# 01_LSH-120.net
KiCad netlist of a schematic drawn in Altium Designer
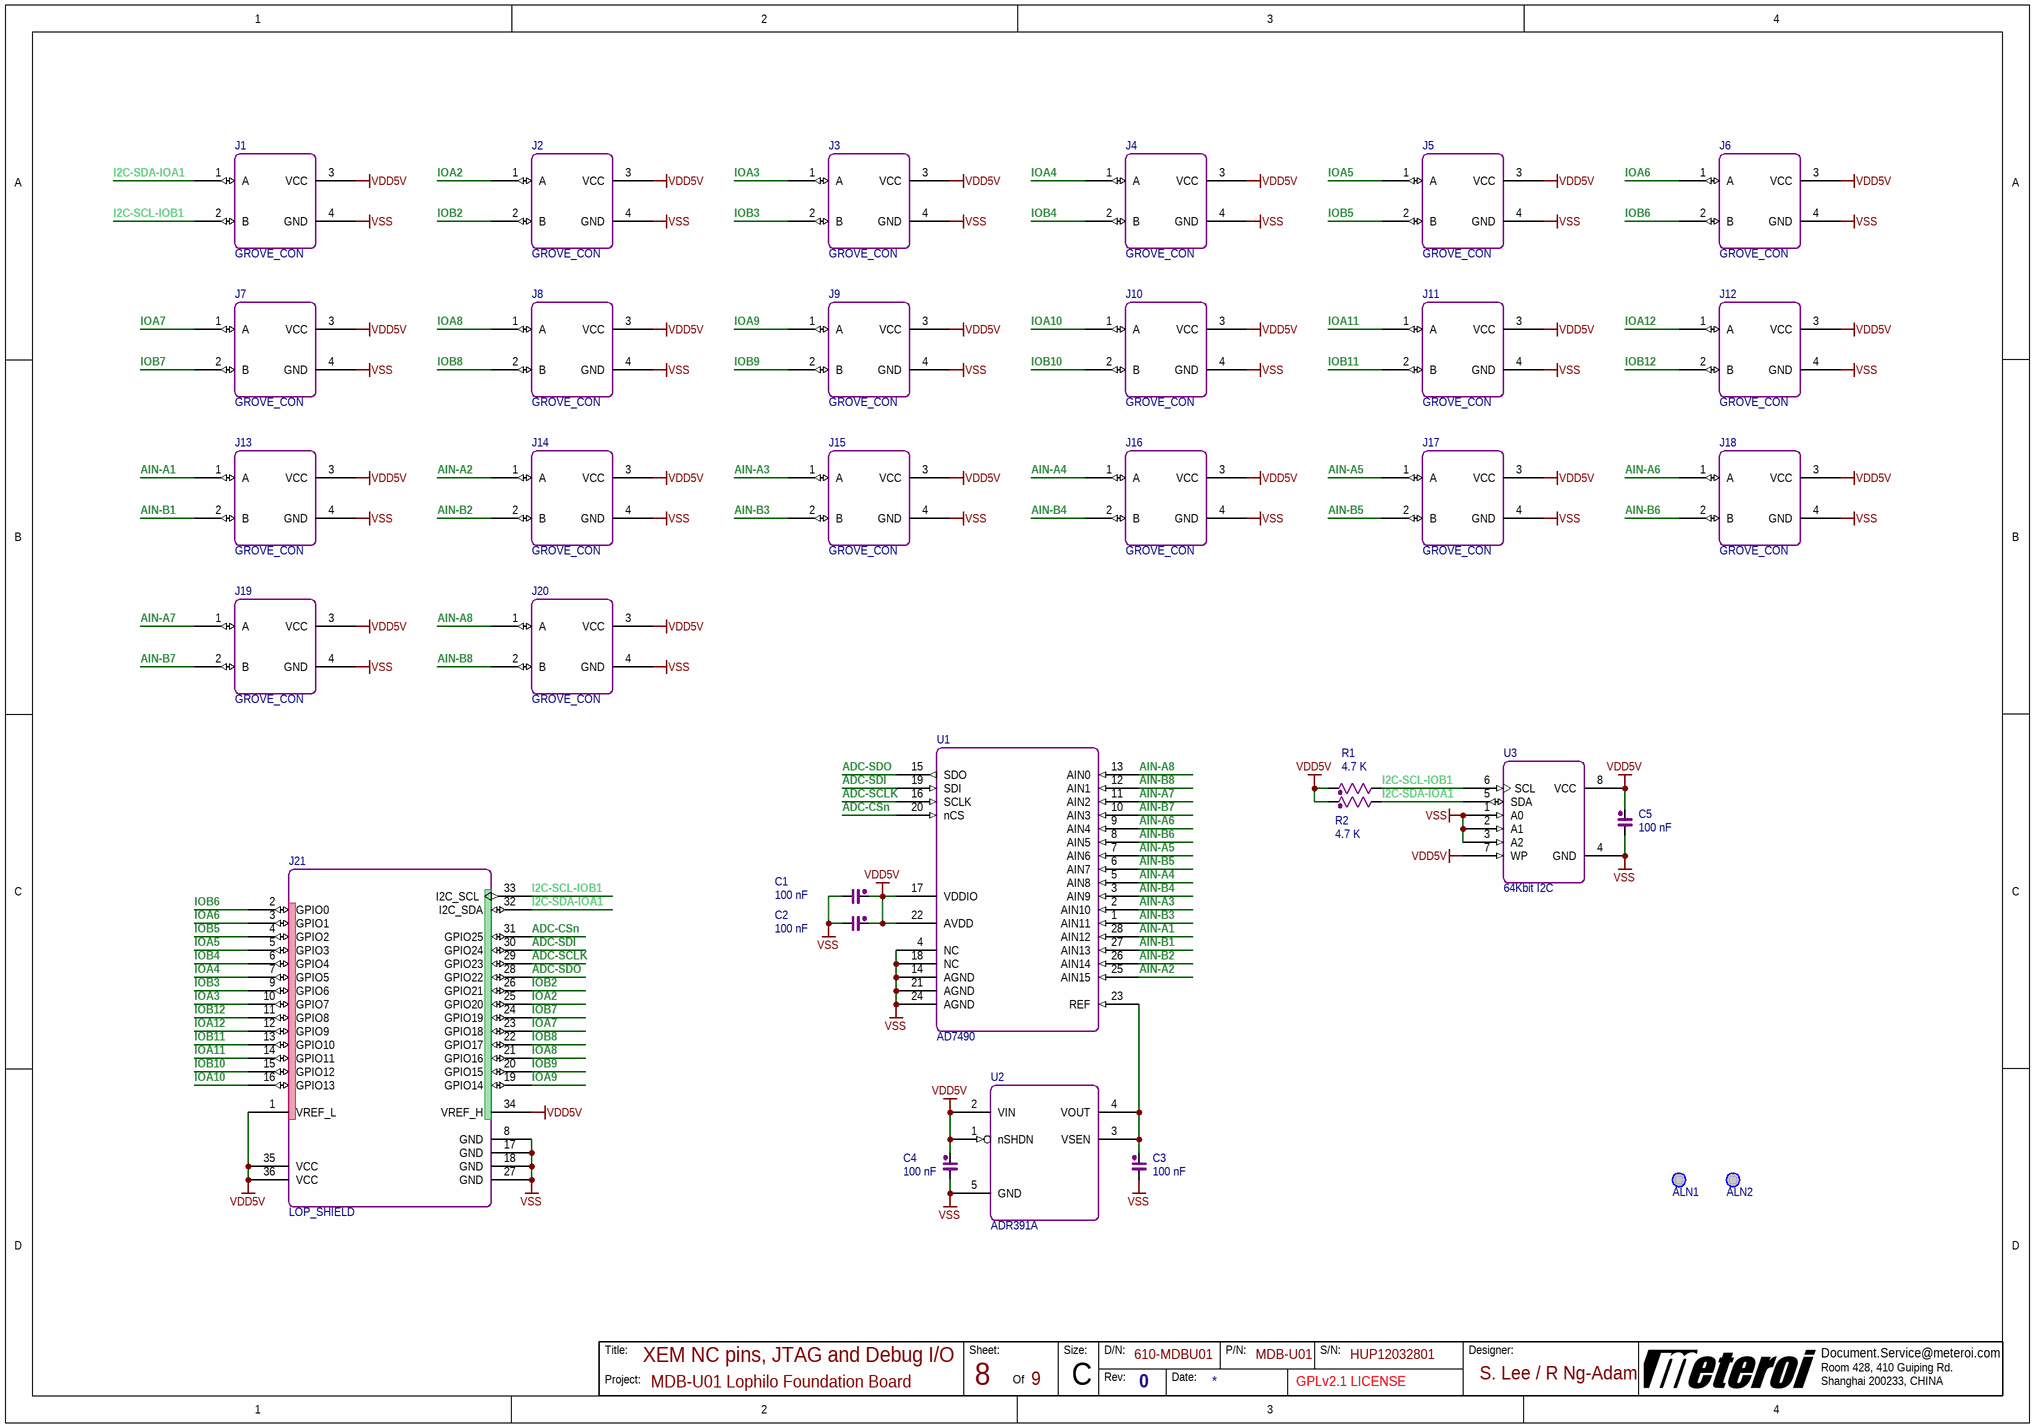
[diagram p0: 01_LSH-120.SchDoc]

(export (version "E")
  (design (tool "Eeschema 10.0.6"))
  (components
    (comp (ref "ALN1")
      (value "Assembly Optical Align")
      (footprint "ALIGN_1")
      (fields
        (field (name "PARTNUMBER") "0")
        (field (name "PUBLISHER") "Cowin")
        (field (name "DESIGNER") "shyul")
      )
      (libsource (lib "PCBElement_Manufacture") (part "ALIGN"))
    )
    (comp (ref "ALN2")
      (value "Assembly Optical Align")
      (footprint "ALIGN_1")
      (fields
        (field (name "PARTNUMBER") "0")
        (field (name "PUBLISHER") "Cowin")
        (field (name "DESIGNER") "shyul")
      )
      (libsource (lib "PCBElement_Manufacture") (part "ALIGN"))
    )
    (comp (ref "C1")
      (value "100 nF")
      (footprint "0603A1")
      (description "Normal Capacitor")
      (fields
        (field (name "PARTNUMBER") "0")
        (field (name "PUBLISHER") "Cowin")
        (field (name "DESIGNER") "shyul")
      )
      (libsource (lib "") (part "CAP_1"))
    )
    (comp (ref "C2")
      (value "100 nF")
      (footprint "0603A1")
      (description "Normal Capacitor")
      (fields
        (field (name "PARTNUMBER") "0")
        (field (name "PUBLISHER") "Cowin")
        (field (name "DESIGNER") "shyul")
      )
      (libsource (lib "") (part "CAP_1"))
    )
    (comp (ref "C3")
      (value "100 nF")
      (footprint "0603A1")
      (description "Normal Capacitor")
      (fields
        (field (name "PARTNUMBER") "0")
        (field (name "PUBLISHER") "Cowin")
        (field (name "DESIGNER") "shyul")
      )
      (libsource (lib "Basc_1_Passive") (part "CAP"))
    )
    (comp (ref "C4")
      (value "100 nF")
      (footprint "0603A1")
      (description "Normal Capacitor")
      (fields
        (field (name "PARTNUMBER") "0")
        (field (name "PUBLISHER") "Cowin")
        (field (name "DESIGNER") "shyul")
      )
      (libsource (lib "Basc_1_Passive") (part "CAP"))
    )
    (comp (ref "C5")
      (value "100 nF")
      (footprint "0603A1")
      (description "Normal Capacitor")
      (fields
        (field (name "PARTNUMBER") "0")
        (field (name "PUBLISHER") "Cowin")
        (field (name "DESIGNER") "shyul")
      )
      (libsource (lib "Basc_1_Passive") (part "CAP"))
    )
    (comp (ref "J1")
      (value "GROVE_CON")
      (footprint "PHB-4A")
      (description "Grove Connector")
      (fields (field (name "PUBLISHER") "Cowin") (field (name "DESIGNER") "shyul"))
      (libsource (lib "PCB_LSH-120") (part "GROVE_CON"))
    )
    (comp (ref "J2")
      (value "GROVE_CON")
      (footprint "PHB-4A")
      (description "Grove Connector")
      (fields (field (name "PUBLISHER") "Cowin") (field (name "DESIGNER") "shyul"))
      (libsource (lib "PCB_LSH-120") (part "GROVE_CON"))
    )
    (comp (ref "J3")
      (value "GROVE_CON")
      (footprint "PHB-4A")
      (description "Grove Connector")
      (fields (field (name "PUBLISHER") "Cowin") (field (name "DESIGNER") "shyul"))
      (libsource (lib "PCB_LSH-120") (part "GROVE_CON"))
    )
    (comp (ref "J4")
      (value "GROVE_CON")
      (footprint "PHB-4A")
      (description "Grove Connector")
      (fields (field (name "PUBLISHER") "Cowin") (field (name "DESIGNER") "shyul"))
      (libsource (lib "PCB_LSH-120") (part "GROVE_CON"))
    )
    (comp (ref "J5")
      (value "GROVE_CON")
      (footprint "PHB-4A")
      (description "Grove Connector")
      (fields (field (name "PUBLISHER") "Cowin") (field (name "DESIGNER") "shyul"))
      (libsource (lib "PCB_LSH-120") (part "GROVE_CON"))
    )
    (comp (ref "J6")
      (value "GROVE_CON")
      (footprint "PHB-4A")
      (description "Grove Connector")
      (fields (field (name "PUBLISHER") "Cowin") (field (name "DESIGNER") "shyul"))
      (libsource (lib "PCB_LSH-120") (part "GROVE_CON"))
    )
    (comp (ref "J7")
      (value "GROVE_CON")
      (footprint "PHB-4A")
      (description "Grove Connector")
      (fields (field (name "PUBLISHER") "Cowin") (field (name "DESIGNER") "shyul"))
      (libsource (lib "PCB_LSH-120") (part "GROVE_CON"))
    )
    (comp (ref "J8")
      (value "GROVE_CON")
      (footprint "PHB-4A")
      (description "Grove Connector")
      (fields (field (name "PUBLISHER") "Cowin") (field (name "DESIGNER") "shyul"))
      (libsource (lib "PCB_LSH-120") (part "GROVE_CON"))
    )
    (comp (ref "J9")
      (value "GROVE_CON")
      (footprint "PHB-4A")
      (description "Grove Connector")
      (fields (field (name "PUBLISHER") "Cowin") (field (name "DESIGNER") "shyul"))
      (libsource (lib "PCB_LSH-120") (part "GROVE_CON"))
    )
    (comp (ref "J10")
      (value "GROVE_CON")
      (footprint "PHB-4A")
      (description "Grove Connector")
      (fields (field (name "PUBLISHER") "Cowin") (field (name "DESIGNER") "shyul"))
      (libsource (lib "PCB_LSH-120") (part "GROVE_CON"))
    )
    (comp (ref "J11")
      (value "GROVE_CON")
      (footprint "PHB-4A")
      (description "Grove Connector")
      (fields (field (name "PUBLISHER") "Cowin") (field (name "DESIGNER") "shyul"))
      (libsource (lib "PCB_LSH-120") (part "GROVE_CON"))
    )
    (comp (ref "J12")
      (value "GROVE_CON")
      (footprint "PHB-4A")
      (description "Grove Connector")
      (fields (field (name "PUBLISHER") "Cowin") (field (name "DESIGNER") "shyul"))
      (libsource (lib "PCB_LSH-120") (part "GROVE_CON"))
    )
    (comp (ref "J13")
      (value "GROVE_CON")
      (footprint "PHB-4A")
      (description "Grove Connector")
      (fields (field (name "PUBLISHER") "Cowin") (field (name "DESIGNER") "shyul"))
      (libsource (lib "PCB_LSH-120") (part "GROVE_CON"))
    )
    (comp (ref "J14")
      (value "GROVE_CON")
      (footprint "PHB-4A")
      (description "Grove Connector")
      (fields (field (name "PUBLISHER") "Cowin") (field (name "DESIGNER") "shyul"))
      (libsource (lib "PCB_LSH-120") (part "GROVE_CON"))
    )
    (comp (ref "J15")
      (value "GROVE_CON")
      (footprint "PHB-4A")
      (description "Grove Connector")
      (fields (field (name "PUBLISHER") "Cowin") (field (name "DESIGNER") "shyul"))
      (libsource (lib "PCB_LSH-120") (part "GROVE_CON"))
    )
    (comp (ref "J16")
      (value "GROVE_CON")
      (footprint "PHB-4A")
      (description "Grove Connector")
      (fields (field (name "PUBLISHER") "Cowin") (field (name "DESIGNER") "shyul"))
      (libsource (lib "PCB_LSH-120") (part "GROVE_CON"))
    )
    (comp (ref "J17")
      (value "GROVE_CON")
      (footprint "PHB-4A")
      (description "Grove Connector")
      (fields (field (name "PUBLISHER") "Cowin") (field (name "DESIGNER") "shyul"))
      (libsource (lib "PCB_LSH-120") (part "GROVE_CON"))
    )
    (comp (ref "J18")
      (value "GROVE_CON")
      (footprint "PHB-4A")
      (description "Grove Connector")
      (fields (field (name "PUBLISHER") "Cowin") (field (name "DESIGNER") "shyul"))
      (libsource (lib "PCB_LSH-120") (part "GROVE_CON"))
    )
    (comp (ref "J19")
      (value "GROVE_CON")
      (footprint "PHB-4A")
      (description "Grove Connector")
      (fields (field (name "PUBLISHER") "Cowin") (field (name "DESIGNER") "shyul"))
      (libsource (lib "PCB_LSH-120") (part "GROVE_CON"))
    )
    (comp (ref "J20")
      (value "GROVE_CON")
      (footprint "PHB-4A")
      (description "Grove Connector")
      (fields (field (name "PUBLISHER") "Cowin") (field (name "DESIGNER") "shyul"))
      (libsource (lib "PCB_LSH-120") (part "GROVE_CON"))
    )
    (comp (ref "J21")
      (value "LOP_SHIELD")
      (footprint "LOP_SHIELD_MOD")
      (description "Lophilo Shield Module Slot")
      (fields (field (name "PUBLISHER") "Cowin") (field (name "DESIGNER") "shyul"))
      (libsource (lib "PCB_LSH-100") (part "LOP_SHIELD_MOD"))
    )
    (comp (ref "R1")
      (value "4.7 K")
      (footprint "0603A2")
      (description "Normal Resistor")
      (fields
        (field (name "PARTNUMBER") "0")
        (field (name "DESIGNER") "shyul")
        (field (name "PUBLISHER") "Cowin")
      )
      (libsource (lib "Basc_1_Passive") (part "RES"))
    )
    (comp (ref "R2")
      (value "4.7 K")
      (footprint "0603A2")
      (description "Normal Resistor")
      (fields
        (field (name "PARTNUMBER") "0")
        (field (name "DESIGNER") "shyul")
        (field (name "PUBLISHER") "Cowin")
      )
      (libsource (lib "Basc_1_Passive") (part "RES"))
    )
    (comp (ref "U1")
      (value "AD7490")
      (footprint "TSSOP-28")
      (description "16 Inputs MUX ADC / 12-Bit 1Msps")
      (fields (field (name "PUBLISHER") "Cowin") (field (name "DESIGNER") "shyul"))
      (libsource (lib "PCB_LSH-120") (part "AD7490"))
    )
    (comp (ref "U2")
      (value "ADR391A")
      (footprint "SOT-23-5")
      (description "16 Inputs MUX ADC / 12-Bit 1Msps")
      (fields
        (field (name "PARTNUMBER") "ADR391AUJZ")
        (field (name "PUBLISHER") "Cowin")
        (field (name "DESIGNER") "shyul")
      )
      (libsource (lib "PCB_LSH-120") (part "ADR391"))
    )
    (comp (ref "U3")
      (value "64Kbit I2C")
      (footprint "SOIC-8S")
      (description "Generic 24 Series I2C ROM")
      (fields
        (field (name "PARTNUMBER") "24C08")
        (field (name "PUBLISHER") "Cowin")
        (field (name "DESIGNER") "shyul")
      )
      (libsource (lib "IC_03_MCU") (part "ROM_I2C_A"))
    )
  )
  (nets
    (net (code "1") (name "/ADC-CSn") (class "Default")
      (node (ref "J21") (pin "31") (pinfunction "GPIO25_31") (pintype "bidirectional"))
      (node (ref "U1") (pin "20") (pinfunction "nCS_20") (pintype "input"))
    )
    (net (code "2") (name "/ADC-SCLK") (class "Default")
      (node (ref "J21") (pin "29") (pinfunction "GPIO23_29") (pintype "bidirectional"))
      (node (ref "U1") (pin "16") (pinfunction "SCLK_16") (pintype "input"))
    )
    (net (code "3") (name "/ADC-SDI") (class "Default")
      (node (ref "J21") (pin "30") (pinfunction "GPIO24_30") (pintype "bidirectional"))
      (node (ref "U1") (pin "19") (pinfunction "SDI_19") (pintype "input"))
    )
    (net (code "4") (name "/ADC-SDO") (class "Default")
      (node (ref "J21") (pin "28") (pinfunction "GPIO22_28") (pintype "bidirectional"))
      (node (ref "U1") (pin "15") (pinfunction "SDO_15") (pintype "output"))
    )
    (net (code "5") (name "/AIN-A1") (class "Default")
      (node (ref "J13") (pin "1") (pinfunction "A_1") (pintype "bidirectional"))
      (node (ref "U1") (pin "28") (pinfunction "AIN12_28") (pintype "input"))
    )
    (net (code "6") (name "/AIN-A2") (class "Default")
      (node (ref "J14") (pin "1") (pinfunction "A_1") (pintype "bidirectional"))
      (node (ref "U1") (pin "25") (pinfunction "AIN15_25") (pintype "input"))
    )
    (net (code "7") (name "/AIN-A3") (class "Default")
      (node (ref "J15") (pin "1") (pinfunction "A_1") (pintype "bidirectional"))
      (node (ref "U1") (pin "2") (pinfunction "AIN10_2") (pintype "input"))
    )
    (net (code "8") (name "/AIN-A4") (class "Default")
      (node (ref "J16") (pin "1") (pinfunction "A_1") (pintype "bidirectional"))
      (node (ref "U1") (pin "5") (pinfunction "AIN8_5") (pintype "input"))
    )
    (net (code "9") (name "/AIN-A5") (class "Default")
      (node (ref "J17") (pin "1") (pinfunction "A_1") (pintype "bidirectional"))
      (node (ref "U1") (pin "7") (pinfunction "AIN6_7") (pintype "input"))
    )
    (net (code "10") (name "/AIN-A6") (class "Default")
      (node (ref "J18") (pin "1") (pinfunction "A_1") (pintype "bidirectional"))
      (node (ref "U1") (pin "9") (pinfunction "AIN4_9") (pintype "input"))
    )
    (net (code "11") (name "/AIN-A7") (class "Default")
      (node (ref "J19") (pin "1") (pinfunction "A_1") (pintype "bidirectional"))
      (node (ref "U1") (pin "11") (pinfunction "AIN2_11") (pintype "input"))
    )
    (net (code "12") (name "/AIN-A8") (class "Default")
      (node (ref "J20") (pin "1") (pinfunction "A_1") (pintype "bidirectional"))
      (node (ref "U1") (pin "13") (pinfunction "AIN0_13") (pintype "input"))
    )
    (net (code "13") (name "/AIN-B1") (class "Default")
      (node (ref "J13") (pin "2") (pinfunction "B_2") (pintype "bidirectional"))
      (node (ref "U1") (pin "27") (pinfunction "AIN13_27") (pintype "input"))
    )
    (net (code "14") (name "/AIN-B2") (class "Default")
      (node (ref "J14") (pin "2") (pinfunction "B_2") (pintype "bidirectional"))
      (node (ref "U1") (pin "26") (pinfunction "AIN14_26") (pintype "input"))
    )
    (net (code "15") (name "/AIN-B3") (class "Default")
      (node (ref "J15") (pin "2") (pinfunction "B_2") (pintype "bidirectional"))
      (node (ref "U1") (pin "1") (pinfunction "AIN11_1") (pintype "input"))
    )
    (net (code "16") (name "/AIN-B4") (class "Default")
      (node (ref "J16") (pin "2") (pinfunction "B_2") (pintype "bidirectional"))
      (node (ref "U1") (pin "3") (pinfunction "AIN9_3") (pintype "input"))
    )
    (net (code "17") (name "/AIN-B5") (class "Default")
      (node (ref "J17") (pin "2") (pinfunction "B_2") (pintype "bidirectional"))
      (node (ref "U1") (pin "6") (pinfunction "AIN7_6") (pintype "input"))
    )
    (net (code "18") (name "/AIN-B6") (class "Default")
      (node (ref "J18") (pin "2") (pinfunction "B_2") (pintype "bidirectional"))
      (node (ref "U1") (pin "8") (pinfunction "AIN5_8") (pintype "input"))
    )
    (net (code "19") (name "/AIN-B7") (class "Default")
      (node (ref "J19") (pin "2") (pinfunction "B_2") (pintype "bidirectional"))
      (node (ref "U1") (pin "10") (pinfunction "AIN3_10") (pintype "input"))
    )
    (net (code "20") (name "/AIN-B8") (class "Default")
      (node (ref "J20") (pin "2") (pinfunction "B_2") (pintype "bidirectional"))
      (node (ref "U1") (pin "12") (pinfunction "AIN1_12") (pintype "input"))
    )
    (net (code "21") (name "/I2C-SCL-IOB1") (class "Default")
      (node (ref "J1") (pin "2") (pinfunction "B_2") (pintype "bidirectional"))
      (node (ref "J21") (pin "33") (pinfunction "I2C_SCL_33") (pintype "output"))
      (node (ref "R1") (pin "1") (pinfunction "1_1") (pintype "passive"))
      (node (ref "U3") (pin "6") (pinfunction "SCL_6") (pintype "input"))
    )
    (net (code "22") (name "/I2C-SDA-IOA1") (class "Default")
      (node (ref "J1") (pin "1") (pinfunction "A_1") (pintype "bidirectional"))
      (node (ref "J21") (pin "32") (pinfunction "I2C_SDA_32") (pintype "bidirectional"))
      (node (ref "R2") (pin "1") (pinfunction "1_1") (pintype "passive"))
      (node (ref "U3") (pin "5") (pinfunction "SDA_5") (pintype "bidirectional"))
    )
    (net (code "23") (name "/IOA2") (class "Default")
      (node (ref "J2") (pin "1") (pinfunction "A_1") (pintype "bidirectional"))
      (node (ref "J21") (pin "25") (pinfunction "GPIO20_25") (pintype "bidirectional"))
    )
    (net (code "24") (name "/IOA3") (class "Default")
      (node (ref "J21") (pin "10") (pinfunction "GPIO7_10") (pintype "bidirectional"))
      (node (ref "J3") (pin "1") (pinfunction "A_1") (pintype "bidirectional"))
    )
    (net (code "25") (name "/IOA4") (class "Default")
      (node (ref "J21") (pin "7") (pinfunction "GPIO5_7") (pintype "bidirectional"))
      (node (ref "J4") (pin "1") (pinfunction "A_1") (pintype "bidirectional"))
    )
    (net (code "26") (name "/IOA5") (class "Default")
      (node (ref "J21") (pin "5") (pinfunction "GPIO3_5") (pintype "bidirectional"))
      (node (ref "J5") (pin "1") (pinfunction "A_1") (pintype "bidirectional"))
    )
    (net (code "27") (name "/IOA6") (class "Default")
      (node (ref "J21") (pin "3") (pinfunction "GPIO1_3") (pintype "bidirectional"))
      (node (ref "J6") (pin "1") (pinfunction "A_1") (pintype "bidirectional"))
    )
    (net (code "28") (name "/IOA7") (class "Default")
      (node (ref "J21") (pin "23") (pinfunction "GPIO18_23") (pintype "bidirectional"))
      (node (ref "J7") (pin "1") (pinfunction "A_1") (pintype "bidirectional"))
    )
    (net (code "29") (name "/IOA8") (class "Default")
      (node (ref "J21") (pin "21") (pinfunction "GPIO16_21") (pintype "bidirectional"))
      (node (ref "J8") (pin "1") (pinfunction "A_1") (pintype "bidirectional"))
    )
    (net (code "30") (name "/IOA9") (class "Default")
      (node (ref "J21") (pin "19") (pinfunction "GPIO14_19") (pintype "bidirectional"))
      (node (ref "J9") (pin "1") (pinfunction "A_1") (pintype "bidirectional"))
    )
    (net (code "31") (name "/IOA10") (class "Default")
      (node (ref "J10") (pin "1") (pinfunction "A_1") (pintype "bidirectional"))
      (node (ref "J21") (pin "16") (pinfunction "GPIO13_16") (pintype "bidirectional"))
    )
    (net (code "32") (name "/IOA11") (class "Default")
      (node (ref "J11") (pin "1") (pinfunction "A_1") (pintype "bidirectional"))
      (node (ref "J21") (pin "14") (pinfunction "GPIO11_14") (pintype "bidirectional"))
    )
    (net (code "33") (name "/IOA12") (class "Default")
      (node (ref "J12") (pin "1") (pinfunction "A_1") (pintype "bidirectional"))
      (node (ref "J21") (pin "12") (pinfunction "GPIO9_12") (pintype "bidirectional"))
    )
    (net (code "34") (name "/IOB2") (class "Default")
      (node (ref "J2") (pin "2") (pinfunction "B_2") (pintype "bidirectional"))
      (node (ref "J21") (pin "26") (pinfunction "GPIO21_26") (pintype "bidirectional"))
    )
    (net (code "35") (name "/IOB3") (class "Default")
      (node (ref "J21") (pin "9") (pinfunction "GPIO6_9") (pintype "bidirectional"))
      (node (ref "J3") (pin "2") (pinfunction "B_2") (pintype "bidirectional"))
    )
    (net (code "36") (name "/IOB4") (class "Default")
      (node (ref "J21") (pin "6") (pinfunction "GPIO4_6") (pintype "bidirectional"))
      (node (ref "J4") (pin "2") (pinfunction "B_2") (pintype "bidirectional"))
    )
    (net (code "37") (name "/IOB5") (class "Default")
      (node (ref "J21") (pin "4") (pinfunction "GPIO2_4") (pintype "bidirectional"))
      (node (ref "J5") (pin "2") (pinfunction "B_2") (pintype "bidirectional"))
    )
    (net (code "38") (name "/IOB6") (class "Default")
      (node (ref "J21") (pin "2") (pinfunction "GPIO0_2") (pintype "bidirectional"))
      (node (ref "J6") (pin "2") (pinfunction "B_2") (pintype "bidirectional"))
    )
    (net (code "39") (name "/IOB7") (class "Default")
      (node (ref "J21") (pin "24") (pinfunction "GPIO19_24") (pintype "bidirectional"))
      (node (ref "J7") (pin "2") (pinfunction "B_2") (pintype "bidirectional"))
    )
    (net (code "40") (name "/IOB8") (class "Default")
      (node (ref "J21") (pin "22") (pinfunction "GPIO17_22") (pintype "bidirectional"))
      (node (ref "J8") (pin "2") (pinfunction "B_2") (pintype "bidirectional"))
    )
    (net (code "41") (name "/IOB9") (class "Default")
      (node (ref "J21") (pin "20") (pinfunction "GPIO15_20") (pintype "bidirectional"))
      (node (ref "J9") (pin "2") (pinfunction "B_2") (pintype "bidirectional"))
    )
    (net (code "42") (name "/IOB10") (class "Default")
      (node (ref "J10") (pin "2") (pinfunction "B_2") (pintype "bidirectional"))
      (node (ref "J21") (pin "15") (pinfunction "GPIO12_15") (pintype "bidirectional"))
    )
    (net (code "43") (name "/IOB11") (class "Default")
      (node (ref "J11") (pin "2") (pinfunction "B_2") (pintype "bidirectional"))
      (node (ref "J21") (pin "13") (pinfunction "GPIO10_13") (pintype "bidirectional"))
    )
    (net (code "44") (name "/IOB12") (class "Default")
      (node (ref "J12") (pin "2") (pinfunction "B_2") (pintype "bidirectional"))
      (node (ref "J21") (pin "11") (pinfunction "GPIO8_11") (pintype "bidirectional"))
    )
    (net (code "45") (name "Net-(U1-REF)") (class "Default")
      (node (ref "C3") (pin "2") (pinfunction "2_2") (pintype "passive"))
      (node (ref "U1") (pin "23") (pinfunction "REF_23") (pintype "input"))
      (node (ref "U2") (pin "3") (pinfunction "VSEN_3") (pintype "passive"))
      (node (ref "U2") (pin "4") (pinfunction "VOUT_4") (pintype "passive"))
    )
    (net (code "46") (name "VDD5V") (class "Default")
      (node (ref "C1") (pin "2") (pinfunction "2_2") (pintype "passive"))
      (node (ref "C2") (pin "2") (pinfunction "2_2") (pintype "passive"))
      (node (ref "C4") (pin "2") (pinfunction "2_2") (pintype "passive"))
      (node (ref "C5") (pin "2") (pinfunction "2_2") (pintype "passive"))
      (node (ref "J1") (pin "3") (pinfunction "VCC_3") (pintype "passive"))
      (node (ref "J10") (pin "3") (pinfunction "VCC_3") (pintype "passive"))
      (node (ref "J11") (pin "3") (pinfunction "VCC_3") (pintype "passive"))
      (node (ref "J12") (pin "3") (pinfunction "VCC_3") (pintype "passive"))
      (node (ref "J13") (pin "3") (pinfunction "VCC_3") (pintype "passive"))
      (node (ref "J14") (pin "3") (pinfunction "VCC_3") (pintype "passive"))
      (node (ref "J15") (pin "3") (pinfunction "VCC_3") (pintype "passive"))
      (node (ref "J16") (pin "3") (pinfunction "VCC_3") (pintype "passive"))
      (node (ref "J17") (pin "3") (pinfunction "VCC_3") (pintype "passive"))
      (node (ref "J18") (pin "3") (pinfunction "VCC_3") (pintype "passive"))
      (node (ref "J19") (pin "3") (pinfunction "VCC_3") (pintype "passive"))
      (node (ref "J2") (pin "3") (pinfunction "VCC_3") (pintype "passive"))
      (node (ref "J20") (pin "3") (pinfunction "VCC_3") (pintype "passive"))
      (node (ref "J21") (pin "1") (pinfunction "VREF_L_1") (pintype "passive"))
      (node (ref "J21") (pin "34") (pinfunction "VREF_H_34") (pintype "passive"))
      (node (ref "J21") (pin "35") (pinfunction "VCC_35") (pintype "power_in"))
      (node (ref "J21") (pin "36") (pinfunction "VCC_36") (pintype "power_in"))
      (node (ref "J3") (pin "3") (pinfunction "VCC_3") (pintype "passive"))
      (node (ref "J4") (pin "3") (pinfunction "VCC_3") (pintype "passive"))
      (node (ref "J5") (pin "3") (pinfunction "VCC_3") (pintype "passive"))
      (node (ref "J6") (pin "3") (pinfunction "VCC_3") (pintype "passive"))
      (node (ref "J7") (pin "3") (pinfunction "VCC_3") (pintype "passive"))
      (node (ref "J8") (pin "3") (pinfunction "VCC_3") (pintype "passive"))
      (node (ref "J9") (pin "3") (pinfunction "VCC_3") (pintype "passive"))
      (node (ref "R1") (pin "2") (pinfunction "2_2") (pintype "passive"))
      (node (ref "R2") (pin "2") (pinfunction "2_2") (pintype "passive"))
      (node (ref "U1") (pin "17") (pinfunction "VDDIO_17") (pintype "passive"))
      (node (ref "U1") (pin "22") (pinfunction "AVDD_22") (pintype "passive"))
      (node (ref "U2") (pin "1") (pinfunction "nSHDN_1") (pintype "input"))
      (node (ref "U2") (pin "2") (pinfunction "VIN_2") (pintype "passive"))
      (node (ref "U3") (pin "7") (pinfunction "WP_7") (pintype "input"))
      (node (ref "U3") (pin "8") (pinfunction "VCC_8") (pintype "power_in"))
    )
    (net (code "47") (name "VSS") (class "Default")
      (node (ref "C1") (pin "1") (pinfunction "1_1") (pintype "passive"))
      (node (ref "C2") (pin "1") (pinfunction "1_1") (pintype "passive"))
      (node (ref "C3") (pin "1") (pinfunction "1_1") (pintype "passive"))
      (node (ref "C4") (pin "1") (pinfunction "1_1") (pintype "passive"))
      (node (ref "C5") (pin "1") (pinfunction "1_1") (pintype "passive"))
      (node (ref "J1") (pin "4") (pinfunction "GND_4") (pintype "passive"))
      (node (ref "J10") (pin "4") (pinfunction "GND_4") (pintype "passive"))
      (node (ref "J11") (pin "4") (pinfunction "GND_4") (pintype "passive"))
      (node (ref "J12") (pin "4") (pinfunction "GND_4") (pintype "passive"))
      (node (ref "J13") (pin "4") (pinfunction "GND_4") (pintype "passive"))
      (node (ref "J14") (pin "4") (pinfunction "GND_4") (pintype "passive"))
      (node (ref "J15") (pin "4") (pinfunction "GND_4") (pintype "passive"))
      (node (ref "J16") (pin "4") (pinfunction "GND_4") (pintype "passive"))
      (node (ref "J17") (pin "4") (pinfunction "GND_4") (pintype "passive"))
      (node (ref "J18") (pin "4") (pinfunction "GND_4") (pintype "passive"))
      (node (ref "J19") (pin "4") (pinfunction "GND_4") (pintype "passive"))
      (node (ref "J2") (pin "4") (pinfunction "GND_4") (pintype "passive"))
      (node (ref "J20") (pin "4") (pinfunction "GND_4") (pintype "passive"))
      (node (ref "J21") (pin "17") (pinfunction "GND_17") (pintype "passive"))
      (node (ref "J21") (pin "18") (pinfunction "GND_18") (pintype "passive"))
      (node (ref "J21") (pin "27") (pinfunction "GND_27") (pintype "passive"))
      (node (ref "J21") (pin "8") (pinfunction "GND_8") (pintype "passive"))
      (node (ref "J3") (pin "4") (pinfunction "GND_4") (pintype "passive"))
      (node (ref "J4") (pin "4") (pinfunction "GND_4") (pintype "passive"))
      (node (ref "J5") (pin "4") (pinfunction "GND_4") (pintype "passive"))
      (node (ref "J6") (pin "4") (pinfunction "GND_4") (pintype "passive"))
      (node (ref "J7") (pin "4") (pinfunction "GND_4") (pintype "passive"))
      (node (ref "J8") (pin "4") (pinfunction "GND_4") (pintype "passive"))
      (node (ref "J9") (pin "4") (pinfunction "GND_4") (pintype "passive"))
      (node (ref "U1") (pin "14") (pinfunction "AGND_14") (pintype "passive"))
      (node (ref "U1") (pin "18") (pinfunction "NC_18") (pintype "passive"))
      (node (ref "U1") (pin "21") (pinfunction "AGND_21") (pintype "passive"))
      (node (ref "U1") (pin "24") (pinfunction "AGND_24") (pintype "passive"))
      (node (ref "U1") (pin "4") (pinfunction "NC_4") (pintype "passive"))
      (node (ref "U2") (pin "5") (pinfunction "GND_5") (pintype "passive"))
      (node (ref "U3") (pin "1") (pinfunction "A0_1") (pintype "input"))
      (node (ref "U3") (pin "2") (pinfunction "A1_2") (pintype "input"))
      (node (ref "U3") (pin "3") (pinfunction "A2_3") (pintype "input"))
      (node (ref "U3") (pin "4") (pinfunction "GND_4") (pintype "power_in"))
    )
  )
)
